# sch.net
KiCad netlist of a schematic drawn in EAGLE
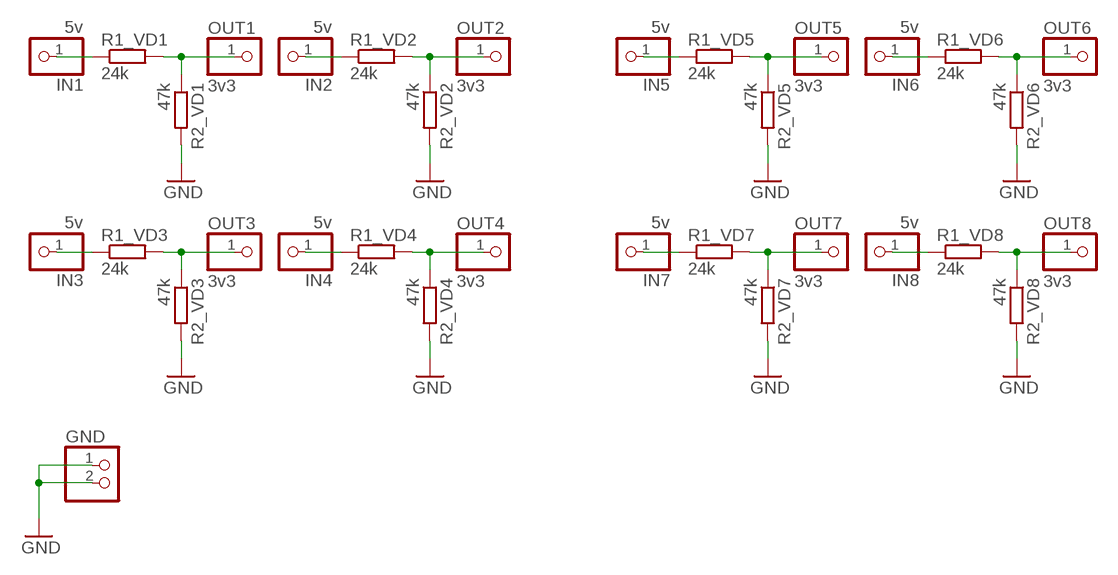
[diagram p0: schematic, sheet 1]

(export (version "E")
  (design (tool "Eeschema 10.0.6"))
  (components
    (comp (ref "GND")
      (value "PINHD-1X2")
      (footprint "eagle-import:1X02")
      (libsource (lib "eagle-import") (part "PINHD-1X2"))
    )
    (comp (ref "IN1")
      (value "5v")
      (footprint "eagle-import:1X01")
      (libsource (lib "eagle-import") (part "PINHD-1X1"))
    )
    (comp (ref "IN2")
      (value "5v")
      (footprint "eagle-import:1X01")
      (libsource (lib "eagle-import") (part "PINHD-1X1"))
    )
    (comp (ref "IN3")
      (value "5v")
      (footprint "eagle-import:1X01")
      (libsource (lib "eagle-import") (part "PINHD-1X1"))
    )
    (comp (ref "IN4")
      (value "5v")
      (footprint "eagle-import:1X01")
      (libsource (lib "eagle-import") (part "PINHD-1X1"))
    )
    (comp (ref "IN5")
      (value "5v")
      (footprint "eagle-import:1X01")
      (libsource (lib "eagle-import") (part "PINHD-1X1"))
    )
    (comp (ref "IN6")
      (value "5v")
      (footprint "eagle-import:1X01")
      (libsource (lib "eagle-import") (part "PINHD-1X1"))
    )
    (comp (ref "IN7")
      (value "5v")
      (footprint "eagle-import:1X01")
      (libsource (lib "eagle-import") (part "PINHD-1X1"))
    )
    (comp (ref "IN8")
      (value "5v")
      (footprint "eagle-import:1X01")
      (libsource (lib "eagle-import") (part "PINHD-1X1"))
    )
    (comp (ref "OUT1")
      (value "3v3")
      (footprint "eagle-import:1X01")
      (libsource (lib "eagle-import") (part "PINHD-1X1"))
    )
    (comp (ref "OUT2")
      (value "3v3")
      (footprint "eagle-import:1X01")
      (libsource (lib "eagle-import") (part "PINHD-1X1"))
    )
    (comp (ref "OUT3")
      (value "3v3")
      (footprint "eagle-import:1X01")
      (libsource (lib "eagle-import") (part "PINHD-1X1"))
    )
    (comp (ref "OUT4")
      (value "3v3")
      (footprint "eagle-import:1X01")
      (libsource (lib "eagle-import") (part "PINHD-1X1"))
    )
    (comp (ref "OUT5")
      (value "3v3")
      (footprint "eagle-import:1X01")
      (libsource (lib "eagle-import") (part "PINHD-1X1"))
    )
    (comp (ref "OUT6")
      (value "3v3")
      (footprint "eagle-import:1X01")
      (libsource (lib "eagle-import") (part "PINHD-1X1"))
    )
    (comp (ref "OUT7")
      (value "3v3")
      (footprint "eagle-import:1X01")
      (libsource (lib "eagle-import") (part "PINHD-1X1"))
    )
    (comp (ref "OUT8")
      (value "3v3")
      (footprint "eagle-import:1X01")
      (libsource (lib "eagle-import") (part "PINHD-1X1"))
    )
    (comp (ref "R1_VD1")
      (value "24k")
      (footprint "eagle-import:R1206")
      (libsource (lib "eagle-import") (part "R-EU_R1206"))
    )
    (comp (ref "R1_VD2")
      (value "24k")
      (footprint "eagle-import:R1206")
      (libsource (lib "eagle-import") (part "R-EU_R1206"))
    )
    (comp (ref "R1_VD3")
      (value "24k")
      (footprint "eagle-import:R1206")
      (libsource (lib "eagle-import") (part "R-EU_R1206"))
    )
    (comp (ref "R1_VD4")
      (value "24k")
      (footprint "eagle-import:R1206")
      (libsource (lib "eagle-import") (part "R-EU_R1206"))
    )
    (comp (ref "R1_VD5")
      (value "24k")
      (footprint "eagle-import:R1206")
      (libsource (lib "eagle-import") (part "R-EU_R1206"))
    )
    (comp (ref "R1_VD6")
      (value "24k")
      (footprint "eagle-import:R1206")
      (libsource (lib "eagle-import") (part "R-EU_R1206"))
    )
    (comp (ref "R1_VD7")
      (value "24k")
      (footprint "eagle-import:R1206")
      (libsource (lib "eagle-import") (part "R-EU_R1206"))
    )
    (comp (ref "R1_VD8")
      (value "24k")
      (footprint "eagle-import:R1206")
      (libsource (lib "eagle-import") (part "R-EU_R1206"))
    )
    (comp (ref "R2_VD1")
      (value "47k")
      (footprint "eagle-import:R1206")
      (libsource (lib "eagle-import") (part "R-EU_R1206"))
    )
    (comp (ref "R2_VD2")
      (value "47k")
      (footprint "eagle-import:R1206")
      (libsource (lib "eagle-import") (part "R-EU_R1206"))
    )
    (comp (ref "R2_VD3")
      (value "47k")
      (footprint "eagle-import:R1206")
      (libsource (lib "eagle-import") (part "R-EU_R1206"))
    )
    (comp (ref "R2_VD4")
      (value "47k")
      (footprint "eagle-import:R1206")
      (libsource (lib "eagle-import") (part "R-EU_R1206"))
    )
    (comp (ref "R2_VD5")
      (value "47k")
      (footprint "eagle-import:R1206")
      (libsource (lib "eagle-import") (part "R-EU_R1206"))
    )
    (comp (ref "R2_VD6")
      (value "47k")
      (footprint "eagle-import:R1206")
      (libsource (lib "eagle-import") (part "R-EU_R1206"))
    )
    (comp (ref "R2_VD7")
      (value "47k")
      (footprint "eagle-import:R1206")
      (libsource (lib "eagle-import") (part "R-EU_R1206"))
    )
    (comp (ref "R2_VD8")
      (value "47k")
      (footprint "eagle-import:R1206")
      (libsource (lib "eagle-import") (part "R-EU_R1206"))
    )
  )
  (nets
    (net (code "1") (name "GND") (class "Default")
      (node (ref "GND") (pin "1") (pinfunction "1_1") (pintype "passive"))
      (node (ref "GND") (pin "2") (pinfunction "2_2") (pintype "passive"))
      (node (ref "R2_VD1") (pin "2") (pinfunction "2_2") (pintype "passive"))
      (node (ref "R2_VD2") (pin "2") (pinfunction "2_2") (pintype "passive"))
      (node (ref "R2_VD3") (pin "2") (pinfunction "2_2") (pintype "passive"))
      (node (ref "R2_VD4") (pin "2") (pinfunction "2_2") (pintype "passive"))
      (node (ref "R2_VD5") (pin "2") (pinfunction "2_2") (pintype "passive"))
      (node (ref "R2_VD6") (pin "2") (pinfunction "2_2") (pintype "passive"))
      (node (ref "R2_VD7") (pin "2") (pinfunction "2_2") (pintype "passive"))
      (node (ref "R2_VD8") (pin "2") (pinfunction "2_2") (pintype "passive"))
    )
    (net (code "2") (name "Net-(IN1-Pad1)") (class "Default")
      (node (ref "IN1") (pin "1") (pinfunction "1_1") (pintype "passive"))
      (node (ref "R1_VD1") (pin "1") (pinfunction "1_1") (pintype "passive"))
    )
    (net (code "3") (name "Net-(IN2-Pad1)") (class "Default")
      (node (ref "IN2") (pin "1") (pinfunction "1_1") (pintype "passive"))
      (node (ref "R1_VD2") (pin "1") (pinfunction "1_1") (pintype "passive"))
    )
    (net (code "4") (name "Net-(IN3-Pad1)") (class "Default")
      (node (ref "IN3") (pin "1") (pinfunction "1_1") (pintype "passive"))
      (node (ref "R1_VD3") (pin "1") (pinfunction "1_1") (pintype "passive"))
    )
    (net (code "5") (name "Net-(IN4-Pad1)") (class "Default")
      (node (ref "IN4") (pin "1") (pinfunction "1_1") (pintype "passive"))
      (node (ref "R1_VD4") (pin "1") (pinfunction "1_1") (pintype "passive"))
    )
    (net (code "6") (name "Net-(IN5-Pad1)") (class "Default")
      (node (ref "IN5") (pin "1") (pinfunction "1_1") (pintype "passive"))
      (node (ref "R1_VD5") (pin "1") (pinfunction "1_1") (pintype "passive"))
    )
    (net (code "7") (name "Net-(IN6-Pad1)") (class "Default")
      (node (ref "IN6") (pin "1") (pinfunction "1_1") (pintype "passive"))
      (node (ref "R1_VD6") (pin "1") (pinfunction "1_1") (pintype "passive"))
    )
    (net (code "8") (name "Net-(IN7-Pad1)") (class "Default")
      (node (ref "IN7") (pin "1") (pinfunction "1_1") (pintype "passive"))
      (node (ref "R1_VD7") (pin "1") (pinfunction "1_1") (pintype "passive"))
    )
    (net (code "9") (name "Net-(IN8-Pad1)") (class "Default")
      (node (ref "IN8") (pin "1") (pinfunction "1_1") (pintype "passive"))
      (node (ref "R1_VD8") (pin "1") (pinfunction "1_1") (pintype "passive"))
    )
    (net (code "10") (name "Net-(OUT1-Pad1)") (class "Default")
      (node (ref "OUT1") (pin "1") (pinfunction "1_1") (pintype "passive"))
      (node (ref "R1_VD1") (pin "2") (pinfunction "2_2") (pintype "passive"))
      (node (ref "R2_VD1") (pin "1") (pinfunction "1_1") (pintype "passive"))
    )
    (net (code "11") (name "Net-(OUT2-Pad1)") (class "Default")
      (node (ref "OUT2") (pin "1") (pinfunction "1_1") (pintype "passive"))
      (node (ref "R1_VD2") (pin "2") (pinfunction "2_2") (pintype "passive"))
      (node (ref "R2_VD2") (pin "1") (pinfunction "1_1") (pintype "passive"))
    )
    (net (code "12") (name "Net-(OUT3-Pad1)") (class "Default")
      (node (ref "OUT3") (pin "1") (pinfunction "1_1") (pintype "passive"))
      (node (ref "R1_VD3") (pin "2") (pinfunction "2_2") (pintype "passive"))
      (node (ref "R2_VD3") (pin "1") (pinfunction "1_1") (pintype "passive"))
    )
    (net (code "13") (name "Net-(OUT4-Pad1)") (class "Default")
      (node (ref "OUT4") (pin "1") (pinfunction "1_1") (pintype "passive"))
      (node (ref "R1_VD4") (pin "2") (pinfunction "2_2") (pintype "passive"))
      (node (ref "R2_VD4") (pin "1") (pinfunction "1_1") (pintype "passive"))
    )
    (net (code "14") (name "Net-(OUT5-Pad1)") (class "Default")
      (node (ref "OUT5") (pin "1") (pinfunction "1_1") (pintype "passive"))
      (node (ref "R1_VD5") (pin "2") (pinfunction "2_2") (pintype "passive"))
      (node (ref "R2_VD5") (pin "1") (pinfunction "1_1") (pintype "passive"))
    )
    (net (code "15") (name "Net-(OUT6-Pad1)") (class "Default")
      (node (ref "OUT6") (pin "1") (pinfunction "1_1") (pintype "passive"))
      (node (ref "R1_VD6") (pin "2") (pinfunction "2_2") (pintype "passive"))
      (node (ref "R2_VD6") (pin "1") (pinfunction "1_1") (pintype "passive"))
    )
    (net (code "16") (name "Net-(OUT7-Pad1)") (class "Default")
      (node (ref "OUT7") (pin "1") (pinfunction "1_1") (pintype "passive"))
      (node (ref "R1_VD7") (pin "2") (pinfunction "2_2") (pintype "passive"))
      (node (ref "R2_VD7") (pin "1") (pinfunction "1_1") (pintype "passive"))
    )
    (net (code "17") (name "Net-(OUT8-Pad1)") (class "Default")
      (node (ref "OUT8") (pin "1") (pinfunction "1_1") (pintype "passive"))
      (node (ref "R1_VD8") (pin "2") (pinfunction "2_2") (pintype "passive"))
      (node (ref "R2_VD8") (pin "1") (pinfunction "1_1") (pintype "passive"))
    )
  )
)
